# GIANTpanda.net
KiCad netlist of a schematic drawn in EAGLE
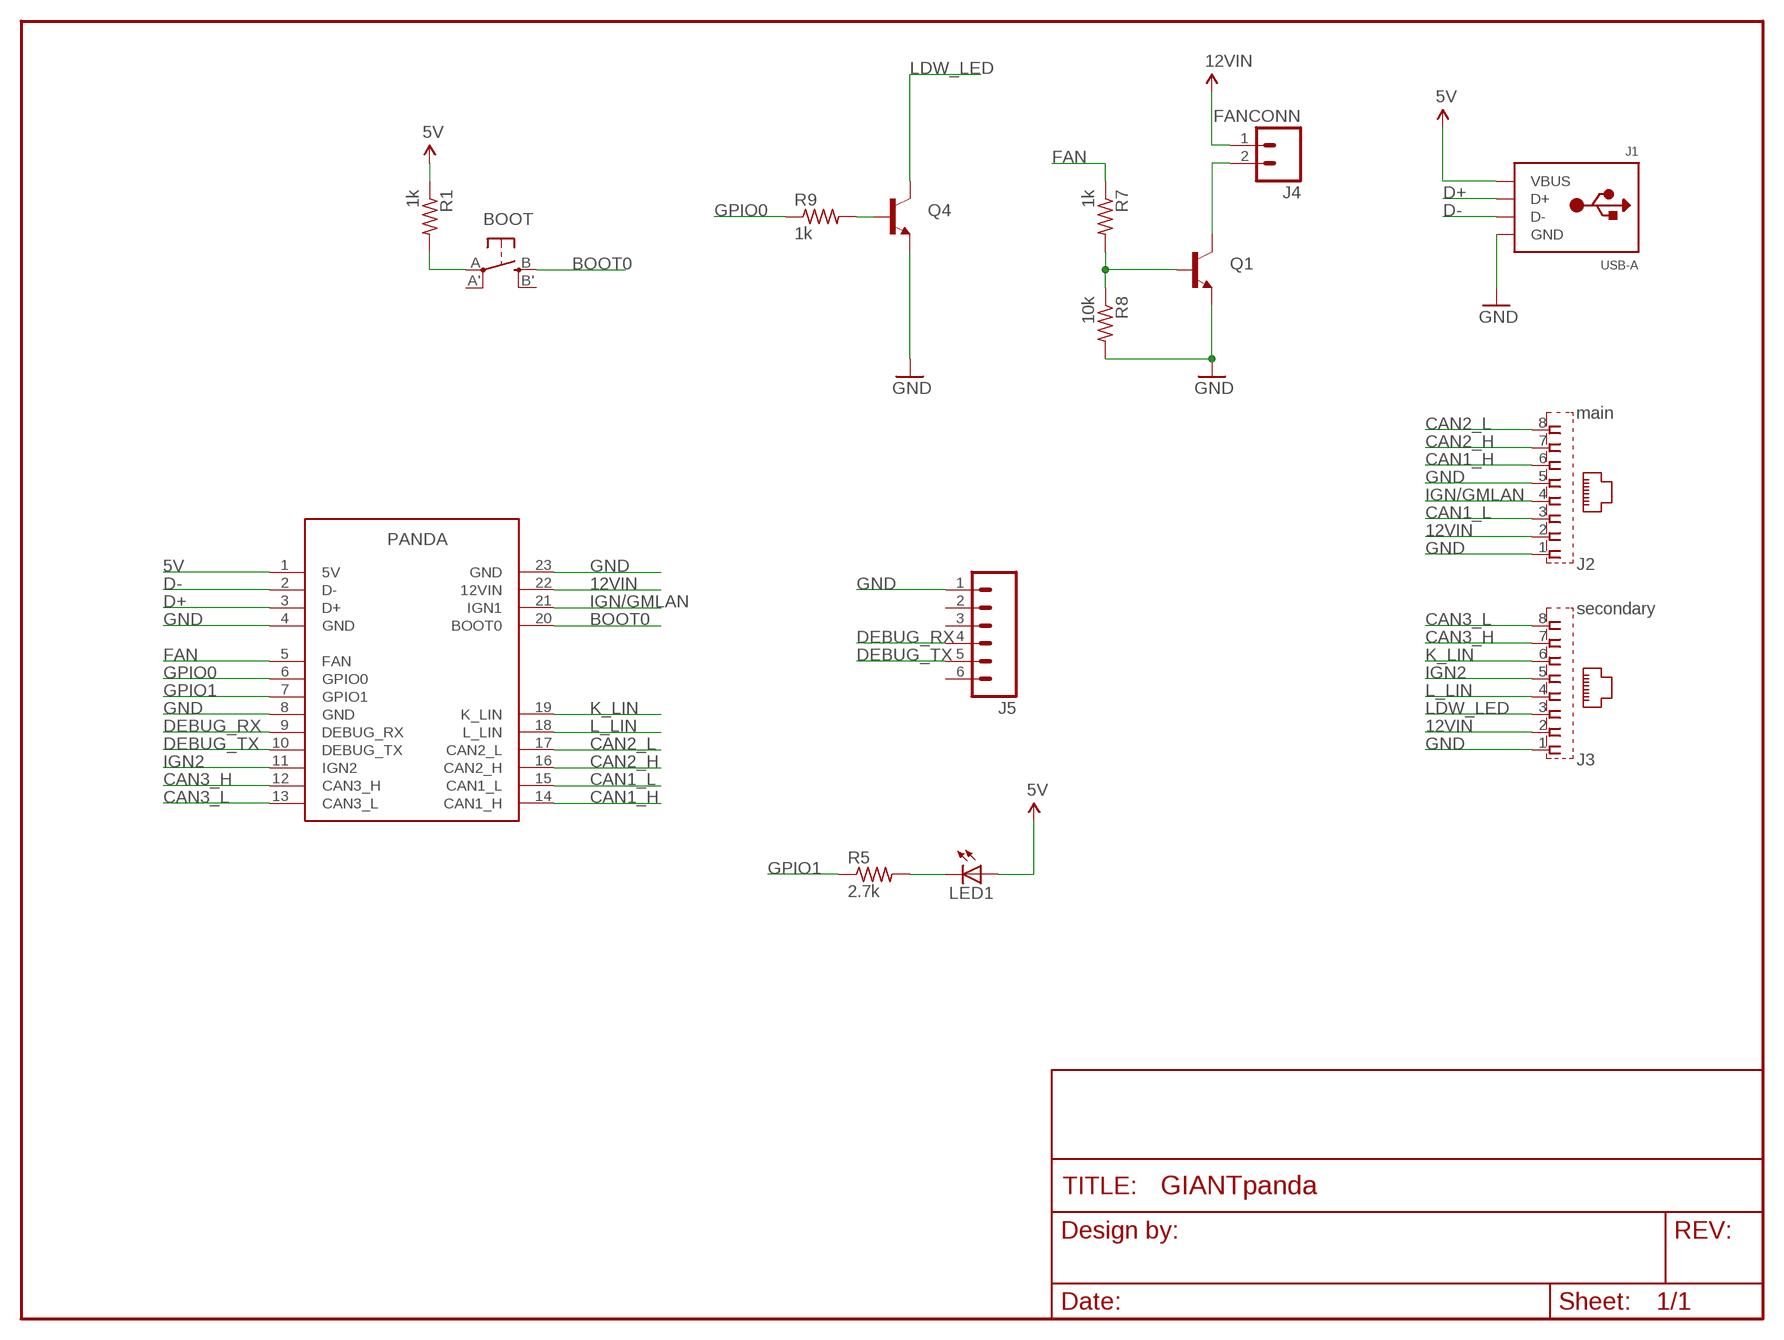
[diagram p0: schematic, sheet 1]

(export (version "E")
  (design (tool "Eeschema 10.0.6"))
  (components
    (comp (ref "BOOT")
      (value "SPST_TACT-EVQQ2")
      (footprint "eagle-import:EVQ-Q2")
      (libsource (lib "eagle-import") (part "SPST_TACT-EVQQ2"))
    )
    (comp (ref "FRAME1")
      (value "FRAME-LETTERNO_PACKAGE")
      (footprint "eagle-import:DUMMY")
      (fields (field (name "DESIGNER") "Nobody"))
      (libsource (lib "eagle-import") (part "FRAME-LETTERNO_PACKAGE"))
    )
    (comp (ref "J1")
      (value "USB-A")
      (footprint "eagle-import:MOLEX_480371000")
      (libsource (lib "eagle-import") (part "USB-A"))
    )
    (comp (ref "J2")
      (value "main")
      (footprint "eagle-import:GLX-S-88M")
      (libsource (lib "eagle-import") (part "VERT_RJ45"))
    )
    (comp (ref "J3")
      (value "secondary")
      (footprint "eagle-import:GLX-S-88M")
      (libsource (lib "eagle-import") (part "VERT_RJ45"))
    )
    (comp (ref "J4")
      (value "FANCONN")
      (footprint "eagle-import:1.25CONN")
      (libsource (lib "eagle-import") (part "FANCONN"))
    )
    (comp (ref "J5")
      (value "M06NO_SILK_YES_STOP")
      (footprint "eagle-import:1X06_NO_SILK_YES_STOP")
      (libsource (lib "eagle-import") (part "M06NO_SILK_YES_STOP"))
    )
    (comp (ref "LED1")
      (value "LEDCHIPLED_0805")
      (footprint "eagle-import:CHIPLED_0805")
      (libsource (lib "eagle-import") (part "LEDCHIPLED_0805"))
    )
    (comp (ref "Q1")
      (value "MMBT2222A")
      (footprint "eagle-import:SOT23-3")
      (libsource (lib "eagle-import") (part "TRANSISTOR_NPNMMBT2222A"))
    )
    (comp (ref "Q4")
      (value "MMBT2222A")
      (footprint "eagle-import:SOT23-3")
      (libsource (lib "eagle-import") (part "TRANSISTOR_NPNMMBT2222A"))
    )
    (comp (ref "R1")
      (value "1k")
      (footprint "eagle-import:0603-R")
      (libsource (lib "eagle-import") (part "R0603"))
    )
    (comp (ref "R5")
      (value "2.7k")
      (footprint "eagle-import:0603-R")
      (libsource (lib "eagle-import") (part "R0603"))
    )
    (comp (ref "R7")
      (value "1k")
      (footprint "eagle-import:0603-R")
      (libsource (lib "eagle-import") (part "R0603"))
    )
    (comp (ref "R8")
      (value "10k")
      (footprint "eagle-import:0603-R")
      (libsource (lib "eagle-import") (part "R0603"))
    )
    (comp (ref "R9")
      (value "1k")
      (footprint "eagle-import:0603-R")
      (libsource (lib "eagle-import") (part "R0603"))
    )
    (comp (ref "U$1")
      (value "PANDA")
      (footprint "eagle-import:PANDA-FOOT")
      (libsource (lib "eagle-import") (part "PANDA"))
    )
  )
  (nets
    (net (code "1") (name "/BOOT0") (class "Default")
      (node (ref "BOOT") (pin "B") (pinfunction "S_B") (pintype "passive"))
      (node (ref "U$1") (pin "20") (pinfunction "BOOT0_20") (pintype "bidirectional"))
    )
    (net (code "2") (name "/CAN1_H") (class "Default")
      (node (ref "J2") (pin "6") (pinfunction "6_6") (pintype "passive"))
      (node (ref "U$1") (pin "14") (pinfunction "CAN1_H_14") (pintype "bidirectional"))
    )
    (net (code "3") (name "/CAN1_L") (class "Default")
      (node (ref "J2") (pin "3") (pinfunction "3_3") (pintype "passive"))
      (node (ref "U$1") (pin "15") (pinfunction "CAN1_L_15") (pintype "bidirectional"))
    )
    (net (code "4") (name "/CAN2_H") (class "Default")
      (node (ref "J2") (pin "7") (pinfunction "7_7") (pintype "passive"))
      (node (ref "U$1") (pin "16") (pinfunction "CAN2_H_16") (pintype "bidirectional"))
    )
    (net (code "5") (name "/CAN2_L") (class "Default")
      (node (ref "J2") (pin "8") (pinfunction "8_8") (pintype "passive"))
      (node (ref "U$1") (pin "17") (pinfunction "CAN2_L_17") (pintype "bidirectional"))
    )
    (net (code "6") (name "/CAN3_H") (class "Default")
      (node (ref "J3") (pin "7") (pinfunction "7_7") (pintype "passive"))
      (node (ref "U$1") (pin "12") (pinfunction "CAN3_H_12") (pintype "bidirectional"))
    )
    (net (code "7") (name "/CAN3_L") (class "Default")
      (node (ref "J3") (pin "8") (pinfunction "8_8") (pintype "passive"))
      (node (ref "U$1") (pin "13") (pinfunction "CAN3_L_13") (pintype "bidirectional"))
    )
    (net (code "8") (name "/D+") (class "Default")
      (node (ref "J1") (pin "3") (pinfunction "D+_3") (pintype "bidirectional"))
      (node (ref "U$1") (pin "3") (pinfunction "D+_3") (pintype "bidirectional"))
    )
    (net (code "9") (name "/D-") (class "Default")
      (node (ref "J1") (pin "2") (pinfunction "D-_2") (pintype "bidirectional"))
      (node (ref "U$1") (pin "2") (pinfunction "D-_2") (pintype "bidirectional"))
    )
    (net (code "10") (name "/DEBUG_RX") (class "Default")
      (node (ref "J5") (pin "4") (pinfunction "4_4") (pintype "passive"))
      (node (ref "U$1") (pin "9") (pinfunction "DEBUG_RX_9") (pintype "bidirectional"))
    )
    (net (code "11") (name "/DEBUG_TX") (class "Default")
      (node (ref "J5") (pin "5") (pinfunction "5_5") (pintype "passive"))
      (node (ref "U$1") (pin "10") (pinfunction "DEBUG_TX_10") (pintype "bidirectional"))
    )
    (net (code "12") (name "/FAN") (class "Default")
      (node (ref "R7") (pin "1") (pinfunction "1_1") (pintype "passive"))
      (node (ref "U$1") (pin "5") (pinfunction "FAN_5") (pintype "bidirectional"))
    )
    (net (code "13") (name "/GPIO0") (class "Default")
      (node (ref "R9") (pin "1") (pinfunction "1_1") (pintype "passive"))
      (node (ref "U$1") (pin "6") (pinfunction "GPIO0_6") (pintype "bidirectional"))
    )
    (net (code "14") (name "/GPIO1") (class "Default")
      (node (ref "R5") (pin "1") (pinfunction "1_1") (pintype "passive"))
      (node (ref "U$1") (pin "7") (pinfunction "GPIO1_7") (pintype "bidirectional"))
    )
    (net (code "15") (name "/IGN2") (class "Default")
      (node (ref "J3") (pin "5") (pinfunction "5_5") (pintype "passive"))
      (node (ref "U$1") (pin "11") (pinfunction "IGN2_11") (pintype "bidirectional"))
    )
    (net (code "16") (name "/IGN{slash}GMLAN") (class "Default")
      (node (ref "J2") (pin "4") (pinfunction "4_4") (pintype "passive"))
      (node (ref "U$1") (pin "21") (pinfunction "IGN1_21") (pintype "bidirectional"))
    )
    (net (code "17") (name "/K_LIN") (class "Default")
      (node (ref "J3") (pin "6") (pinfunction "6_6") (pintype "passive"))
      (node (ref "U$1") (pin "19") (pinfunction "K_LIN_19") (pintype "bidirectional"))
    )
    (net (code "18") (name "/LDW_LED") (class "Default")
      (node (ref "J3") (pin "3") (pinfunction "3_3") (pintype "passive"))
      (node (ref "Q4") (pin "3") (pinfunction "C_3") (pintype "passive"))
    )
    (net (code "19") (name "/L_LIN") (class "Default")
      (node (ref "J3") (pin "4") (pinfunction "4_4") (pintype "passive"))
      (node (ref "U$1") (pin "18") (pinfunction "L_LIN_18") (pintype "bidirectional"))
    )
    (net (code "20") (name "5V") (class "Default")
      (node (ref "J1") (pin "1") (pinfunction "VBUS_1") (pintype "power_in"))
      (node (ref "LED1") (pin "A") (pinfunction "A_A") (pintype "passive"))
      (node (ref "R1") (pin "1") (pinfunction "1_1") (pintype "passive"))
      (node (ref "U$1") (pin "1") (pinfunction "5V_1") (pintype "bidirectional"))
    )
    (net (code "21") (name "12VIN") (class "Default")
      (node (ref "J2") (pin "2") (pinfunction "2_2") (pintype "passive"))
      (node (ref "J3") (pin "2") (pinfunction "2_2") (pintype "passive"))
      (node (ref "J4") (pin "1") (pinfunction "1_1") (pintype "passive"))
      (node (ref "U$1") (pin "22") (pinfunction "12VIN_22") (pintype "bidirectional"))
    )
    (net (code "22") (name "GND") (class "Default")
      (node (ref "J1") (pin "4") (pinfunction "GND_4") (pintype "power_in"))
      (node (ref "J2") (pin "1") (pinfunction "1_1") (pintype "passive"))
      (node (ref "J2") (pin "5") (pinfunction "5_5") (pintype "passive"))
      (node (ref "J3") (pin "1") (pinfunction "1_1") (pintype "passive"))
      (node (ref "J5") (pin "1") (pinfunction "1_1") (pintype "passive"))
      (node (ref "Q1") (pin "2") (pinfunction "E_2") (pintype "passive"))
      (node (ref "Q4") (pin "2") (pinfunction "E_2") (pintype "passive"))
      (node (ref "R8") (pin "2") (pinfunction "2_2") (pintype "passive"))
      (node (ref "U$1") (pin "23") (pinfunction "GND_23") (pintype "bidirectional"))
      (node (ref "U$1") (pin "4") (pinfunction "GND_4") (pintype "bidirectional"))
      (node (ref "U$1") (pin "8") (pinfunction "GND_8") (pintype "bidirectional"))
    )
    (net (code "23") (name "Net-(BOOT-P)") (class "Default")
      (node (ref "BOOT") (pin "A") (pinfunction "P_A") (pintype "passive"))
      (node (ref "R1") (pin "2") (pinfunction "2_2") (pintype "passive"))
    )
    (net (code "24") (name "Net-(LED1-PadC)") (class "Default")
      (node (ref "LED1") (pin "C") (pinfunction "C_C") (pintype "passive"))
      (node (ref "R5") (pin "2") (pinfunction "2_2") (pintype "passive"))
    )
    (net (code "25") (name "Net-(Q1-B)") (class "Default")
      (node (ref "Q1") (pin "1") (pinfunction "B_1") (pintype "passive"))
      (node (ref "R7") (pin "2") (pinfunction "2_2") (pintype "passive"))
      (node (ref "R8") (pin "1") (pinfunction "1_1") (pintype "passive"))
    )
    (net (code "26") (name "Net-(Q1-C)") (class "Default")
      (node (ref "J4") (pin "2") (pinfunction "2_2") (pintype "passive"))
      (node (ref "Q1") (pin "3") (pinfunction "C_3") (pintype "passive"))
    )
    (net (code "27") (name "Net-(Q4-B)") (class "Default")
      (node (ref "Q4") (pin "1") (pinfunction "B_1") (pintype "passive"))
      (node (ref "R9") (pin "2") (pinfunction "2_2") (pintype "passive"))
    )
    (net (code "28") (name "unconnected-(BOOT-P1-PadA')") (class "Default")
      (node (ref "BOOT") (pin "A'") (pinfunction "P1_A'") (pintype "passive"))
    )
    (net (code "29") (name "unconnected-(BOOT-S1-PadB')") (class "Default")
      (node (ref "BOOT") (pin "B'") (pinfunction "S1_B'") (pintype "passive"))
    )
    (net (code "30") (name "unconnected-(J5-Pad2)") (class "Default")
      (node (ref "J5") (pin "2") (pinfunction "2_2") (pintype "passive"))
    )
    (net (code "31") (name "unconnected-(J5-Pad3)") (class "Default")
      (node (ref "J5") (pin "3") (pinfunction "3_3") (pintype "passive"))
    )
    (net (code "32") (name "unconnected-(J5-Pad6)") (class "Default")
      (node (ref "J5") (pin "6") (pinfunction "6_6") (pintype "passive"))
    )
  )
)
